# uC.net
KiCad netlist of a schematic drawn in Altium Designer
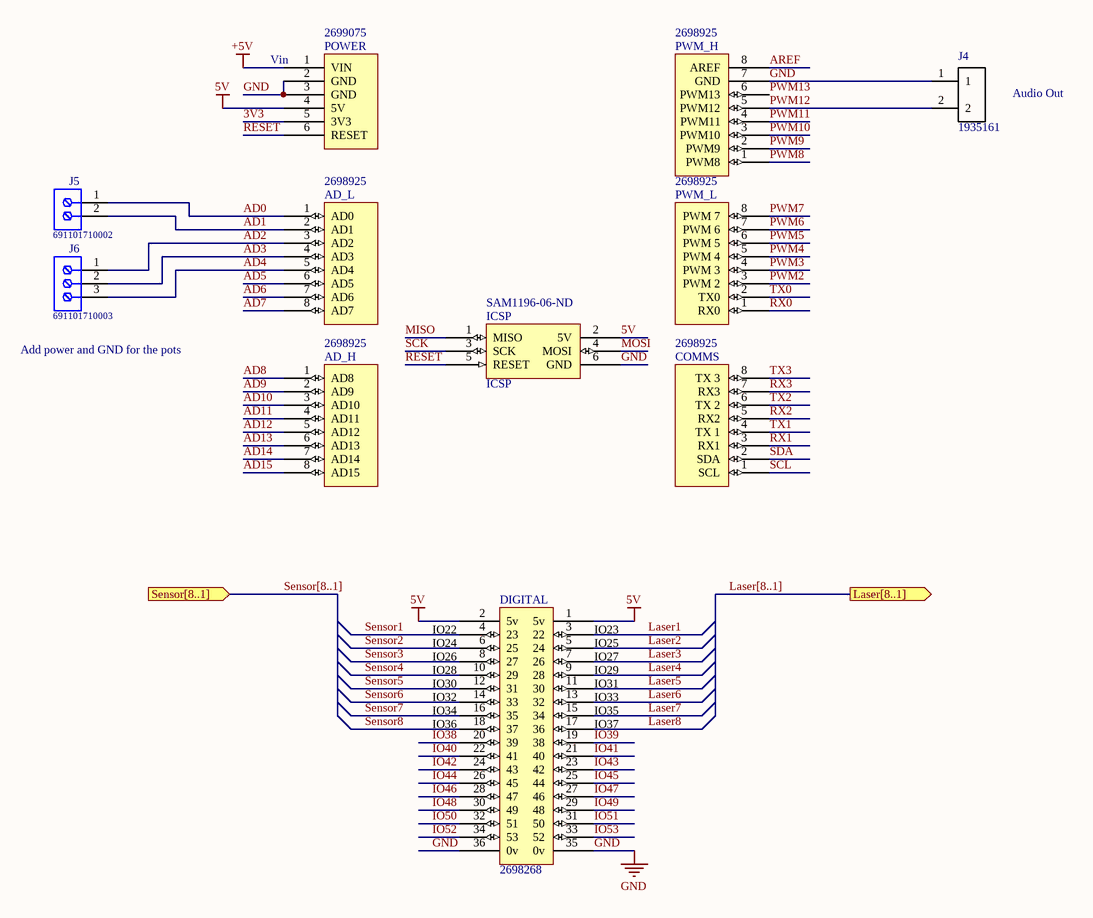
[diagram p0: uC.SchDoc]

(export (version "E")
  (design (tool "Eeschema 10.0.6"))
  (components
    (comp (ref "AD_H")
      (value "AD_H")
      (footprint "Header 8x1 8.5mm")
      (fields (field (name "SUPPLIER PART NUMBER 4") "2698925"))
      (libsource (lib "Header") (part "AD_H"))
    )
    (comp (ref "AD_L")
      (value "AD_L")
      (footprint "Header 8x1 8.5mm")
      (fields (field (name "SUPPLIER PART NUMBER 5") "2698925"))
      (libsource (lib "Header") (part "AD_L"))
    )
    (comp (ref "COMMS")
      (value "Communication")
      (footprint "Header 8x1 8.5mm")
      (fields (field (name "SUPPLIER PART NUMBER 4") "2698925"))
      (libsource (lib "Header") (part "Communication"))
    )
    (comp (ref "DIGITAL")
      (value "IO_36")
      (footprint "HEADER 36X 8MM")
      (fields (field (name "SUPPLIER PART NUMBER 5") "2698268"))
      (libsource (lib "Header") (part "IO_36"))
    )
    (comp (ref "ICSP")
      (value "ICSP")
      (footprint "ICSP")
      (fields (field (name "SUPPLIER PART NUMBER 5") "SAM1196-06-ND"))
      (libsource (lib "Header") (part "ICSP"))
    )
    (comp (ref "J4")
      (value "1935161")
      (footprint "PHOENIX_1935161")
      (description "Conn Terminal Blocks 2 POS 5mm Solder ST Thru-Hole 16A")
      (fields (field (name "DIGI-KEY_PART_NUMBER") "277-1667-ND") (field (name "MF") "Phoenix Contact"))
      (libsource (lib "Laser") (part "1935161"))
    )
    (comp (ref "J5")
      (value "691101710002")
      (footprint "691101710002")
      (description "Series 101 - 5.00 mm Horizontal Entry Modular with Pressure Clamp WR-TBL, 2 pin")
      (fields (field (name "PUBLISHER") "Wurth Elektronik"))
      (libsource (lib "ALTIUM-WIRE-PROTECTOR-CONTBL1-rev18b") (part "691101710002"))
    )
    (comp (ref "J6")
      (value "691101710003")
      (footprint "691101710003")
      (description "Series 101 - 5.00 mm Horizontal Entry Modular with Pressure Clamp WR-TBL, 3 pin")
      (fields (field (name "PUBLISHER") "Wurth Elektronik"))
      (libsource (lib "ALTIUM-WIRE-PROTECTOR-CONTBL1-rev18b") (part "691101710003"))
    )
    (comp (ref "POWER")
      (value "POWER")
      (footprint "Header 6x1 8.5mm")
      (fields (field (name "SUPPLIER PART NUMBER 2") "2699075"))
      (libsource (lib "Header") (part "POWER"))
    )
    (comp (ref "PWM_H")
      (value "PWM_H")
      (footprint "Header 8x1 8.5mm")
      (fields (field (name "SUPPLIER PART NUMBER 4") "2698925"))
      (libsource (lib "Header") (part "PWM_H"))
    )
    (comp (ref "PWM_L")
      (value "PWM_L")
      (footprint "Header 8x1 8.5mm")
      (fields (field (name "SUPPLIER PART NUMBER 4") "2698925"))
      (libsource (lib "Header") (part "PWM_L"))
    )
  )
  (nets
    (net (code "1") (name "+5V") (class "Default")
      (node (ref "POWER") (pin "1") (pinfunction "VIN_1") (pintype "power_in"))
    )
    (net (code "2") (name "/3V3") (class "Default")
      (node (ref "POWER") (pin "5") (pinfunction "3V3_5") (pintype "power_in"))
    )
    (net (code "3") (name "/AD0") (class "Default")
      (node (ref "AD_L") (pin "1") (pinfunction "AD0_1") (pintype "bidirectional"))
      (node (ref "J5") (pin "1") (pinfunction "1_1") (pintype "passive"))
    )
    (net (code "4") (name "/AD1") (class "Default")
      (node (ref "AD_L") (pin "2") (pinfunction "AD1_2") (pintype "bidirectional"))
      (node (ref "J5") (pin "2") (pinfunction "2_2") (pintype "passive"))
    )
    (net (code "5") (name "/AD2") (class "Default")
      (node (ref "AD_L") (pin "3") (pinfunction "AD2_3") (pintype "bidirectional"))
      (node (ref "J6") (pin "1") (pinfunction "1_1") (pintype "passive"))
    )
    (net (code "6") (name "/AD3") (class "Default")
      (node (ref "AD_L") (pin "4") (pinfunction "AD3_4") (pintype "bidirectional"))
      (node (ref "J6") (pin "2") (pinfunction "2_2") (pintype "passive"))
    )
    (net (code "7") (name "/AD4") (class "Default")
      (node (ref "AD_L") (pin "5") (pinfunction "AD4_5") (pintype "bidirectional"))
      (node (ref "J6") (pin "3") (pinfunction "3_3") (pintype "passive"))
    )
    (net (code "8") (name "/AD5") (class "Default")
      (node (ref "AD_L") (pin "6") (pinfunction "AD5_6") (pintype "bidirectional"))
    )
    (net (code "9") (name "/AD6") (class "Default")
      (node (ref "AD_L") (pin "7") (pinfunction "AD6_7") (pintype "bidirectional"))
    )
    (net (code "10") (name "/AD7") (class "Default")
      (node (ref "AD_L") (pin "8") (pinfunction "AD7_8") (pintype "bidirectional"))
    )
    (net (code "11") (name "/AD8") (class "Default")
      (node (ref "AD_H") (pin "1") (pinfunction "AD8_1") (pintype "bidirectional"))
    )
    (net (code "12") (name "/AD9") (class "Default")
      (node (ref "AD_H") (pin "2") (pinfunction "AD9_2") (pintype "bidirectional"))
    )
    (net (code "13") (name "/AD10") (class "Default")
      (node (ref "AD_H") (pin "3") (pinfunction "AD10_3") (pintype "bidirectional"))
    )
    (net (code "14") (name "/AD11") (class "Default")
      (node (ref "AD_H") (pin "4") (pinfunction "AD11_4") (pintype "bidirectional"))
    )
    (net (code "15") (name "/AD12") (class "Default")
      (node (ref "AD_H") (pin "5") (pinfunction "AD12_5") (pintype "bidirectional"))
    )
    (net (code "16") (name "/AD13") (class "Default")
      (node (ref "AD_H") (pin "6") (pinfunction "AD13_6") (pintype "bidirectional"))
    )
    (net (code "17") (name "/AD14") (class "Default")
      (node (ref "AD_H") (pin "7") (pinfunction "AD14_7") (pintype "bidirectional"))
    )
    (net (code "18") (name "/AD15") (class "Default")
      (node (ref "AD_H") (pin "8") (pinfunction "AD15_8") (pintype "bidirectional"))
    )
    (net (code "19") (name "/AREF") (class "Default")
      (node (ref "PWM_H") (pin "8") (pinfunction "AREF_8") (pintype "passive"))
    )
    (net (code "20") (name "/IO38") (class "Default")
      (node (ref "DIGITAL") (pin "20") (pinfunction "39_20") (pintype "bidirectional"))
    )
    (net (code "21") (name "/IO39") (class "Default")
      (node (ref "DIGITAL") (pin "19") (pinfunction "38_19") (pintype "bidirectional"))
    )
    (net (code "22") (name "/IO40") (class "Default")
      (node (ref "DIGITAL") (pin "22") (pinfunction "41_22") (pintype "bidirectional"))
    )
    (net (code "23") (name "/IO41") (class "Default")
      (node (ref "DIGITAL") (pin "21") (pinfunction "40_21") (pintype "bidirectional"))
    )
    (net (code "24") (name "/IO42") (class "Default")
      (node (ref "DIGITAL") (pin "24") (pinfunction "43_24") (pintype "bidirectional"))
    )
    (net (code "25") (name "/IO43") (class "Default")
      (node (ref "DIGITAL") (pin "23") (pinfunction "42_23") (pintype "bidirectional"))
    )
    (net (code "26") (name "/IO44") (class "Default")
      (node (ref "DIGITAL") (pin "26") (pinfunction "45_26") (pintype "bidirectional"))
    )
    (net (code "27") (name "/IO45") (class "Default")
      (node (ref "DIGITAL") (pin "25") (pinfunction "44_25") (pintype "bidirectional"))
    )
    (net (code "28") (name "/IO46") (class "Default")
      (node (ref "DIGITAL") (pin "28") (pinfunction "47_28") (pintype "bidirectional"))
    )
    (net (code "29") (name "/IO47") (class "Default")
      (node (ref "DIGITAL") (pin "27") (pinfunction "46_27") (pintype "bidirectional"))
    )
    (net (code "30") (name "/IO48") (class "Default")
      (node (ref "DIGITAL") (pin "30") (pinfunction "49_30") (pintype "bidirectional"))
    )
    (net (code "31") (name "/IO49") (class "Default")
      (node (ref "DIGITAL") (pin "29") (pinfunction "48_29") (pintype "bidirectional"))
    )
    (net (code "32") (name "/IO50") (class "Default")
      (node (ref "DIGITAL") (pin "32") (pinfunction "51_32") (pintype "bidirectional"))
    )
    (net (code "33") (name "/IO51") (class "Default")
      (node (ref "DIGITAL") (pin "31") (pinfunction "50_31") (pintype "bidirectional"))
    )
    (net (code "34") (name "/IO52") (class "Default")
      (node (ref "DIGITAL") (pin "34") (pinfunction "53_34") (pintype "bidirectional"))
    )
    (net (code "35") (name "/IO53") (class "Default")
      (node (ref "DIGITAL") (pin "33") (pinfunction "52_33") (pintype "bidirectional"))
    )
    (net (code "36") (name "/Laser1") (class "Default")
      (node (ref "DIGITAL") (pin "3") (pinfunction "22_3") (pintype "bidirectional"))
    )
    (net (code "37") (name "/Laser2") (class "Default")
      (node (ref "DIGITAL") (pin "5") (pinfunction "24_5") (pintype "bidirectional"))
    )
    (net (code "38") (name "/Laser3") (class "Default")
      (node (ref "DIGITAL") (pin "7") (pinfunction "26_7") (pintype "bidirectional"))
    )
    (net (code "39") (name "/Laser4") (class "Default")
      (node (ref "DIGITAL") (pin "9") (pinfunction "28_9") (pintype "bidirectional"))
    )
    (net (code "40") (name "/Laser5") (class "Default")
      (node (ref "DIGITAL") (pin "11") (pinfunction "30_11") (pintype "bidirectional"))
    )
    (net (code "41") (name "/Laser6") (class "Default")
      (node (ref "DIGITAL") (pin "13") (pinfunction "32_13") (pintype "bidirectional"))
    )
    (net (code "42") (name "/Laser7") (class "Default")
      (node (ref "DIGITAL") (pin "15") (pinfunction "34_15") (pintype "bidirectional"))
    )
    (net (code "43") (name "/Laser8") (class "Default")
      (node (ref "DIGITAL") (pin "17") (pinfunction "36_17") (pintype "bidirectional"))
    )
    (net (code "45") (name "/MISO") (class "Default")
      (node (ref "ICSP") (pin "1") (pinfunction "MISO_1") (pintype "bidirectional"))
    )
    (net (code "46") (name "/MOSI") (class "Default")
      (node (ref "ICSP") (pin "4") (pinfunction "MOSI_4") (pintype "bidirectional"))
    )
    (net (code "47") (name "/PWM2") (class "Default")
      (node (ref "PWM_L") (pin "3") (pinfunction "PWM_2_3") (pintype "bidirectional"))
    )
    (net (code "48") (name "/PWM3") (class "Default")
      (node (ref "PWM_L") (pin "4") (pinfunction "PWM_3_4") (pintype "bidirectional"))
    )
    (net (code "49") (name "/PWM4") (class "Default")
      (node (ref "PWM_L") (pin "5") (pinfunction "PWM_4_5") (pintype "bidirectional"))
    )
    (net (code "50") (name "/PWM5") (class "Default")
      (node (ref "PWM_L") (pin "6") (pinfunction "PWM_5_6") (pintype "bidirectional"))
    )
    (net (code "51") (name "/PWM6") (class "Default")
      (node (ref "PWM_L") (pin "7") (pinfunction "PWM_6_7") (pintype "bidirectional"))
    )
    (net (code "52") (name "/PWM7") (class "Default")
      (node (ref "PWM_L") (pin "8") (pinfunction "PWM_7_8") (pintype "bidirectional"))
    )
    (net (code "53") (name "/PWM8") (class "Default")
      (node (ref "PWM_H") (pin "1") (pinfunction "PWM8_1") (pintype "bidirectional"))
    )
    (net (code "54") (name "/PWM9") (class "Default")
      (node (ref "PWM_H") (pin "2") (pinfunction "PWM9_2") (pintype "bidirectional"))
    )
    (net (code "55") (name "/PWM10") (class "Default")
      (node (ref "PWM_H") (pin "3") (pinfunction "PWM10_3") (pintype "bidirectional"))
    )
    (net (code "56") (name "/PWM11") (class "Default")
      (node (ref "PWM_H") (pin "4") (pinfunction "PWM11_4") (pintype "bidirectional"))
    )
    (net (code "57") (name "/PWM12") (class "Default")
      (node (ref "J4") (pin "2") (pinfunction "2_2") (pintype "passive"))
      (node (ref "PWM_H") (pin "5") (pinfunction "PWM12_5") (pintype "bidirectional"))
    )
    (net (code "58") (name "/PWM13") (class "Default")
      (node (ref "PWM_H") (pin "6") (pinfunction "PWM13_6") (pintype "bidirectional"))
    )
    (net (code "59") (name "/RESET") (class "Default")
      (node (ref "ICSP") (pin "5") (pinfunction "RESET_5") (pintype "input"))
      (node (ref "POWER") (pin "6") (pinfunction "RESET_6") (pintype "passive"))
    )
    (net (code "60") (name "/RX0") (class "Default")
      (node (ref "PWM_L") (pin "1") (pinfunction "RX0_1") (pintype "bidirectional"))
    )
    (net (code "61") (name "/RX1") (class "Default")
      (node (ref "COMMS") (pin "3") (pinfunction "RX1_3") (pintype "bidirectional"))
    )
    (net (code "62") (name "/RX2") (class "Default")
      (node (ref "COMMS") (pin "5") (pinfunction "RX2_5") (pintype "bidirectional"))
    )
    (net (code "63") (name "/RX3") (class "Default")
      (node (ref "COMMS") (pin "7") (pinfunction "RX3_7") (pintype "bidirectional"))
    )
    (net (code "64") (name "/SCK") (class "Default")
      (node (ref "ICSP") (pin "3") (pinfunction "SCK_3") (pintype "bidirectional"))
    )
    (net (code "65") (name "/SCL") (class "Default")
      (node (ref "COMMS") (pin "1") (pinfunction "SCL_1") (pintype "bidirectional"))
    )
    (net (code "66") (name "/SDA") (class "Default")
      (node (ref "COMMS") (pin "2") (pinfunction "SDA_2") (pintype "bidirectional"))
    )
    (net (code "67") (name "/Sensor1") (class "Default")
      (node (ref "DIGITAL") (pin "4") (pinfunction "23_4") (pintype "bidirectional"))
    )
    (net (code "68") (name "/Sensor2") (class "Default")
      (node (ref "DIGITAL") (pin "6") (pinfunction "25_6") (pintype "bidirectional"))
    )
    (net (code "69") (name "/Sensor3") (class "Default")
      (node (ref "DIGITAL") (pin "8") (pinfunction "27_8") (pintype "bidirectional"))
    )
    (net (code "70") (name "/Sensor4") (class "Default")
      (node (ref "DIGITAL") (pin "10") (pinfunction "29_10") (pintype "bidirectional"))
    )
    (net (code "71") (name "/Sensor5") (class "Default")
      (node (ref "DIGITAL") (pin "12") (pinfunction "31_12") (pintype "bidirectional"))
    )
    (net (code "72") (name "/Sensor6") (class "Default")
      (node (ref "DIGITAL") (pin "14") (pinfunction "33_14") (pintype "bidirectional"))
    )
    (net (code "73") (name "/Sensor7") (class "Default")
      (node (ref "DIGITAL") (pin "16") (pinfunction "35_16") (pintype "bidirectional"))
    )
    (net (code "74") (name "/Sensor8") (class "Default")
      (node (ref "DIGITAL") (pin "18") (pinfunction "37_18") (pintype "bidirectional"))
    )
    (net (code "76") (name "/TX0") (class "Default")
      (node (ref "PWM_L") (pin "2") (pinfunction "TX0_2") (pintype "bidirectional"))
    )
    (net (code "77") (name "/TX1") (class "Default")
      (node (ref "COMMS") (pin "4") (pinfunction "TX_1_4") (pintype "bidirectional"))
    )
    (net (code "78") (name "/TX2") (class "Default")
      (node (ref "COMMS") (pin "6") (pinfunction "TX_2_6") (pintype "bidirectional"))
    )
    (net (code "79") (name "/TX3") (class "Default")
      (node (ref "COMMS") (pin "8") (pinfunction "TX_3_8") (pintype "bidirectional"))
    )
    (net (code "80") (name "5V") (class "Default")
      (node (ref "DIGITAL") (pin "1") (pinfunction "5v_1") (pintype "power_in"))
      (node (ref "DIGITAL") (pin "2") (pinfunction "5v_2") (pintype "power_in"))
      (node (ref "ICSP") (pin "2") (pinfunction "5V_2") (pintype "power_in"))
      (node (ref "POWER") (pin "4") (pinfunction "5V_4") (pintype "power_in"))
    )
    (net (code "81") (name "GND") (class "Default")
      (node (ref "DIGITAL") (pin "35") (pinfunction "0v_35") (pintype "power_in"))
      (node (ref "DIGITAL") (pin "36") (pinfunction "0v_36") (pintype "power_in"))
      (node (ref "ICSP") (pin "6") (pinfunction "GND_6") (pintype "power_in"))
      (node (ref "J4") (pin "1") (pinfunction "1_1") (pintype "passive"))
      (node (ref "POWER") (pin "2") (pinfunction "GND_2") (pintype "power_in"))
      (node (ref "POWER") (pin "3") (pinfunction "GND_3") (pintype "power_in"))
      (node (ref "PWM_H") (pin "7") (pinfunction "GND_7") (pintype "power_in"))
    )
  )
)
